# PROYECTO_PCB_final.net
KiCad netlist of a schematic drawn in EAGLE
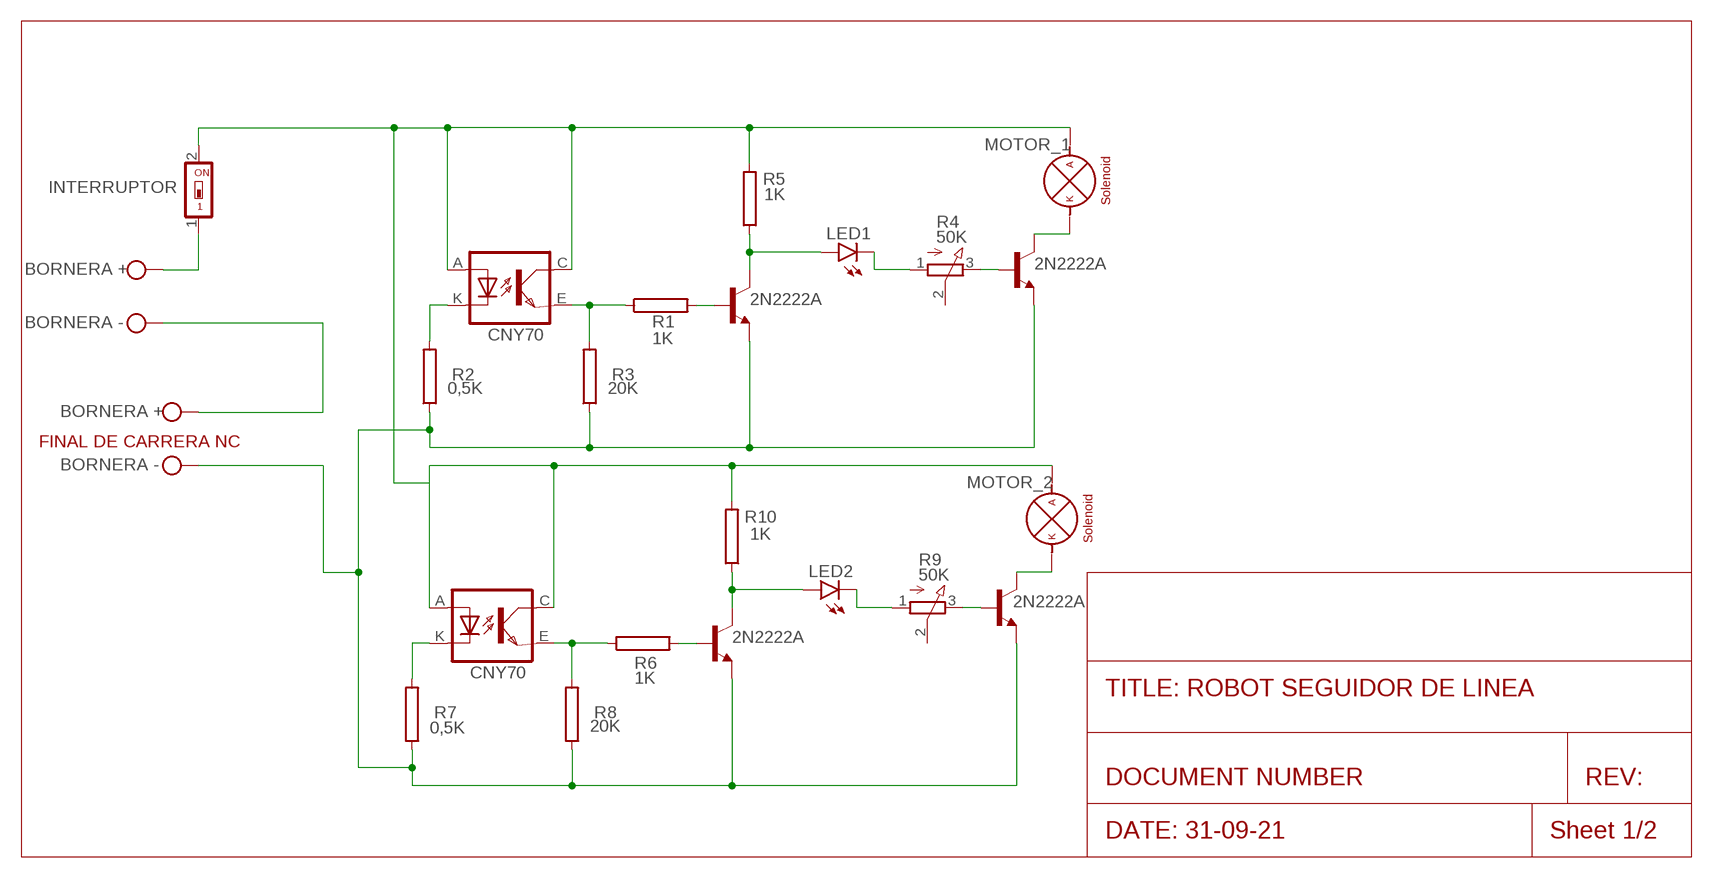
[diagram p0: schematic, sheet 1]

(export (version "E")
  (design (tool "Eeschema 10.0.6"))
  (components
    (comp (ref "BORNERA_+")
      (value "AK300/2")
      (footprint "eagle-import:AK300_2")
      (libsource (lib "eagle-import") (part "AK300/2"))
    )
    (comp (ref "BORNERA_+1")
      (value "AK300/2")
      (footprint "eagle-import:AK300_2")
      (libsource (lib "eagle-import") (part "AK300/2"))
    )
    (comp (ref "INTERRUPTOR")
      (value "SWS001")
      (footprint "eagle-import:SMS-001")
      (libsource (lib "eagle-import") (part "SWS001"))
    )
    (comp (ref "LED1")
      (value "TLLY4400")
      (footprint "eagle-import:LED3MM")
      (fields (field (name "MF") "VISHAY SEMICONDUCTOR"))
      (libsource (lib "eagle-import") (part "TLLY4400"))
    )
    (comp (ref "LED2")
      (value "TLLY4400")
      (footprint "eagle-import:LED3MM")
      (fields (field (name "MF") "VISHAY SEMICONDUCTOR"))
      (libsource (lib "eagle-import") (part "TLLY4400"))
    )
    (comp (ref "MOTOR_1")
      (value "-MOTOR")
      (footprint "eagle-import:CON2")
      (libsource (lib "eagle-import") (part "-MOTOR"))
    )
    (comp (ref "MOTOR_2")
      (value "-MOTOR")
      (footprint "eagle-import:CON2")
      (libsource (lib "eagle-import") (part "-MOTOR"))
    )
    (comp (ref "Q1")
      (value "2N2222A")
      (footprint "eagle-import:TO18")
      (libsource (lib "eagle-import") (part "2N2222A"))
    )
    (comp (ref "Q2")
      (value "2N2222A")
      (footprint "eagle-import:TO18")
      (libsource (lib "eagle-import") (part "2N2222A"))
    )
    (comp (ref "Q3")
      (value "2N2222A")
      (footprint "eagle-import:TO18")
      (libsource (lib "eagle-import") (part "2N2222A"))
    )
    (comp (ref "Q4")
      (value "2N2222A")
      (footprint "eagle-import:TO18")
      (libsource (lib "eagle-import") (part "2N2222A"))
    )
    (comp (ref "R1")
      (value "RMG100-V")
      (footprint "eagle-import:TO-247-2V")
      (libsource (lib "eagle-import") (part "RMG100-V"))
    )
    (comp (ref "R2")
      (value "RMG100-V")
      (footprint "eagle-import:TO-247-2V")
      (libsource (lib "eagle-import") (part "RMG100-V"))
    )
    (comp (ref "R3")
      (value "RMG100-V")
      (footprint "eagle-import:TO-247-2V")
      (libsource (lib "eagle-import") (part "RMG100-V"))
    )
    (comp (ref "R4")
      (value "50K")
      (footprint "eagle-import:3RP_1610N")
      (libsource (lib "eagle-import") (part "3RP/1610N"))
    )
    (comp (ref "R5")
      (value "RMG100-V")
      (footprint "eagle-import:TO-247-2V")
      (libsource (lib "eagle-import") (part "RMG100-V"))
    )
    (comp (ref "R6")
      (value "RMG100-V")
      (footprint "eagle-import:TO-247-2V")
      (libsource (lib "eagle-import") (part "RMG100-V"))
    )
    (comp (ref "R7")
      (value "RMG100-V")
      (footprint "eagle-import:TO-247-2V")
      (libsource (lib "eagle-import") (part "RMG100-V"))
    )
    (comp (ref "R8")
      (value "RMG100-V")
      (footprint "eagle-import:TO-247-2V")
      (libsource (lib "eagle-import") (part "RMG100-V"))
    )
    (comp (ref "R9")
      (value "50K")
      (footprint "eagle-import:3RP_1610N")
      (libsource (lib "eagle-import") (part "3RP/1610N"))
    )
    (comp (ref "R10")
      (value "RMG100-V")
      (footprint "eagle-import:TO-247-2V")
      (libsource (lib "eagle-import") (part "RMG100-V"))
    )
    (comp (ref "U$1")
      (value "CNY70")
      (footprint "eagle-import:4")
      (libsource (lib "eagle-import") (part "CNY70"))
    )
    (comp (ref "U$3")
      (value "CNY70")
      (footprint "eagle-import:4")
      (libsource (lib "eagle-import") (part "CNY70"))
    )
  )
  (nets
    (net (code "1") (name "Net-(BORNERA_+1A-KL)") (class "Default")
      (node (ref "BORNERA_+") (pin "2") (pinfunction "KL_2") (pintype "passive"))
      (node (ref "BORNERA_+1") (pin "1") (pinfunction "KL_1") (pintype "passive"))
    )
    (net (code "2") (name "Net-(BORNERA_+1B-KL)") (class "Default")
      (node (ref "BORNERA_+1") (pin "2") (pinfunction "KL_2") (pintype "passive"))
      (node (ref "Q1") (pin "1") (pinfunction "E_1") (pintype "passive"))
      (node (ref "Q2") (pin "1") (pinfunction "E_1") (pintype "passive"))
      (node (ref "Q3") (pin "1") (pinfunction "E_1") (pintype "passive"))
      (node (ref "Q4") (pin "1") (pinfunction "E_1") (pintype "passive"))
      (node (ref "R2") (pin "1") (pinfunction "1_1") (pintype "passive"))
      (node (ref "R3") (pin "1") (pinfunction "1_1") (pintype "passive"))
      (node (ref "R7") (pin "1") (pinfunction "1_1") (pintype "passive"))
      (node (ref "R8") (pin "1") (pinfunction "1_1") (pintype "passive"))
    )
    (net (code "3") (name "Net-(BORNERA_+A-KL)") (class "Default")
      (node (ref "BORNERA_+") (pin "1") (pinfunction "KL_1") (pintype "passive"))
      (node (ref "INTERRUPTOR") (pin "1") (pinfunction "1_1") (pintype "passive"))
    )
    (net (code "4") (name "Net-(LED1-C)") (class "Default")
      (node (ref "LED1") (pin "K") (pinfunction "C_K") (pintype "passive"))
      (node (ref "R4") (pin "1") (pinfunction "A_1") (pintype "passive"))
    )
    (net (code "5") (name "Net-(LED2-C)") (class "Default")
      (node (ref "LED2") (pin "K") (pinfunction "C_K") (pintype "passive"))
      (node (ref "R9") (pin "1") (pinfunction "A_1") (pintype "passive"))
    )
    (net (code "6") (name "Net-(MOTOR_1-+)") (class "Default")
      (node (ref "INTERRUPTOR") (pin "2") (pinfunction "2_2") (pintype "passive"))
      (node (ref "MOTOR_1") (pin "P$1") (pinfunction "+_P$1") (pintype "passive"))
      (node (ref "MOTOR_2") (pin "P$1") (pinfunction "+_P$1") (pintype "passive"))
      (node (ref "R10") (pin "2") (pinfunction "2_2") (pintype "passive"))
      (node (ref "R5") (pin "2") (pinfunction "2_2") (pintype "passive"))
      (node (ref "U$1") (pin "A") (pinfunction "A_A") (pintype "passive"))
      (node (ref "U$1") (pin "C") (pinfunction "COL_C") (pintype "passive"))
      (node (ref "U$3") (pin "A") (pinfunction "A_A") (pintype "passive"))
      (node (ref "U$3") (pin "C") (pinfunction "COL_C") (pintype "passive"))
    )
    (net (code "7") (name "Net-(MOTOR_1--)") (class "Default")
      (node (ref "MOTOR_1") (pin "P$2") (pinfunction "-_P$2") (pintype "passive"))
      (node (ref "Q2") (pin "3") (pinfunction "C_3") (pintype "passive"))
    )
    (net (code "8") (name "Net-(MOTOR_2--)") (class "Default")
      (node (ref "MOTOR_2") (pin "P$2") (pinfunction "-_P$2") (pintype "passive"))
      (node (ref "Q4") (pin "3") (pinfunction "C_3") (pintype "passive"))
    )
    (net (code "9") (name "Net-(Q1-B)") (class "Default")
      (node (ref "Q1") (pin "2") (pinfunction "B_2") (pintype "passive"))
      (node (ref "R1") (pin "2") (pinfunction "2_2") (pintype "passive"))
    )
    (net (code "10") (name "Net-(Q1-C)") (class "Default")
      (node (ref "LED1") (pin "A") (pinfunction "A_A") (pintype "passive"))
      (node (ref "Q1") (pin "3") (pinfunction "C_3") (pintype "passive"))
      (node (ref "R5") (pin "1") (pinfunction "1_1") (pintype "passive"))
    )
    (net (code "11") (name "Net-(Q2-B)") (class "Default")
      (node (ref "Q2") (pin "2") (pinfunction "B_2") (pintype "passive"))
      (node (ref "R4") (pin "3") (pinfunction "E_3") (pintype "passive"))
    )
    (net (code "12") (name "Net-(Q3-B)") (class "Default")
      (node (ref "Q3") (pin "2") (pinfunction "B_2") (pintype "passive"))
      (node (ref "R6") (pin "2") (pinfunction "2_2") (pintype "passive"))
    )
    (net (code "13") (name "Net-(Q3-C)") (class "Default")
      (node (ref "LED2") (pin "A") (pinfunction "A_A") (pintype "passive"))
      (node (ref "Q3") (pin "3") (pinfunction "C_3") (pintype "passive"))
      (node (ref "R10") (pin "1") (pinfunction "1_1") (pintype "passive"))
    )
    (net (code "14") (name "Net-(Q4-B)") (class "Default")
      (node (ref "Q4") (pin "2") (pinfunction "B_2") (pintype "passive"))
      (node (ref "R9") (pin "3") (pinfunction "E_3") (pintype "passive"))
    )
    (net (code "15") (name "Net-(U$1-C)") (class "Default")
      (node (ref "R2") (pin "2") (pinfunction "2_2") (pintype "passive"))
      (node (ref "U$1") (pin "K") (pinfunction "C_K") (pintype "passive"))
    )
    (net (code "16") (name "Net-(U$1-EMI)") (class "Default")
      (node (ref "R1") (pin "1") (pinfunction "1_1") (pintype "passive"))
      (node (ref "R3") (pin "2") (pinfunction "2_2") (pintype "passive"))
      (node (ref "U$1") (pin "E") (pinfunction "EMI_E") (pintype "passive"))
    )
    (net (code "17") (name "Net-(U$3-C)") (class "Default")
      (node (ref "R7") (pin "2") (pinfunction "2_2") (pintype "passive"))
      (node (ref "U$3") (pin "K") (pinfunction "C_K") (pintype "passive"))
    )
    (net (code "18") (name "Net-(U$3-EMI)") (class "Default")
      (node (ref "R6") (pin "1") (pinfunction "1_1") (pintype "passive"))
      (node (ref "R8") (pin "2") (pinfunction "2_2") (pintype "passive"))
      (node (ref "U$3") (pin "E") (pinfunction "EMI_E") (pintype "passive"))
    )
    (net (code "19") (name "unconnected-(R4-S-Pad2)") (class "Default")
      (node (ref "R4") (pin "2") (pinfunction "S_2") (pintype "passive"))
    )
    (net (code "20") (name "unconnected-(R9-S-Pad2)") (class "Default")
      (node (ref "R9") (pin "2") (pinfunction "S_2") (pintype "passive"))
    )
  )
)
